# Volant5_Power.net
KiCad netlist of a schematic drawn in Altium Designer
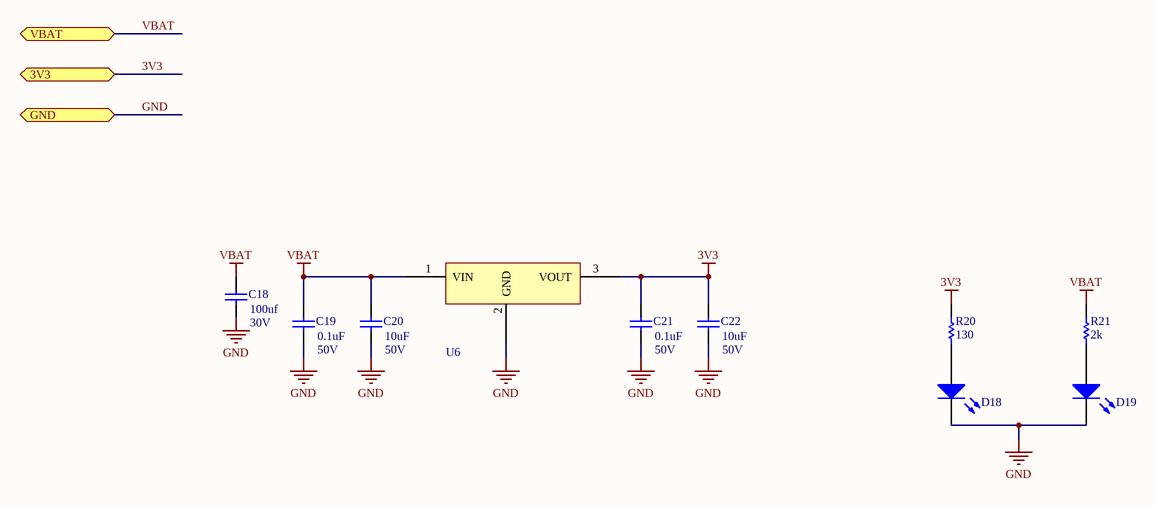
[diagram p0: Volant5.Power.SchDoc]

(export (version "E")
  (design (tool "Eeschema 10.0.6"))
  (components
    (comp (ref "C18")
      (value "100uf")
      (footprint "CS-0603")
      (fields
        (field (name "TOLERANCE") "10%")
        (field (name "VOLTAGE") "30V")
        (field (name "Comment") "CS - CAPACITOR")
      )
      (libsource (lib "CHINOOK_LIBRARY") (part "CS - CAPACITOR"))
    )
    (comp (ref "C19")
      (value "0.1uF")
      (footprint "CS-0603")
      (fields
        (field (name "TOLERANCE") "10%")
        (field (name "VOLTAGE") "50V")
        (field (name "Comment") "CS - CAPACITOR")
      )
      (libsource (lib "CHINOOK_LIBRARY") (part "CS - CAPACITOR"))
    )
    (comp (ref "C20")
      (value "10uF")
      (footprint "CS-0603")
      (fields
        (field (name "TOLERANCE") "10%")
        (field (name "VOLTAGE") "50V")
        (field (name "Comment") "CS - CAPACITOR")
      )
      (libsource (lib "CHINOOK_LIBRARY") (part "CS - CAPACITOR"))
    )
    (comp (ref "C21")
      (value "0.1uF")
      (footprint "CS-0603")
      (fields
        (field (name "TOLERANCE") "10%")
        (field (name "VOLTAGE") "50V")
        (field (name "Comment") "CS - CAPACITOR")
      )
      (libsource (lib "CHINOOK_LIBRARY") (part "CS - CAPACITOR"))
    )
    (comp (ref "C22")
      (value "10uF")
      (footprint "CS-0603")
      (fields
        (field (name "TOLERANCE") "10%")
        (field (name "VOLTAGE") "50V")
        (field (name "Comment") "CS - CAPACITOR")
      )
      (libsource (lib "CHINOOK_LIBRARY") (part "CS - CAPACITOR"))
    )
    (comp (ref "D18")
      (value "LED - NORMAL LED")
      (footprint "LED-0805 YELLOW")
      (libsource (lib "CHINOOK_LIBRARY") (part "LED - NORMAL LED"))
    )
    (comp (ref "D19")
      (value "LED - NORMAL LED")
      (footprint "LED-0805 YELLOW")
      (libsource (lib "CHINOOK_LIBRARY") (part "LED - NORMAL LED"))
    )
    (comp (ref "R20")
      (value "130")
      (footprint "RS-0603")
      (fields
        (field (name "TOLERANCE") "RES TOL")
        (field (name "POWER") "RES POWER")
        (field (name "Comment") "RS - RESISTOR")
      )
      (libsource (lib "CHINOOK_LIBRARY") (part "RS - RESISTOR"))
    )
    (comp (ref "R21")
      (value "2k")
      (footprint "RS-0603")
      (fields
        (field (name "TOLERANCE") "RES TOL")
        (field (name "POWER") "RES POWER")
        (field (name "Comment") "RS - RESISTOR")
      )
      (libsource (lib "CHINOOK_LIBRARY") (part "RS - RESISTOR"))
    )
    (comp (ref "U6")
      (value "OKI-78SR")
      (footprint "IC-OKI78SR-RA")
      (libsource (lib "CHINOOK_LIBRARY") (part "IC - OKI-78SR"))
    )
  )
  (nets
    (net (code "1") (name "3V3") (class "Default")
      (node (ref "C21") (pin "2") (pinfunction "2_2") (pintype "passive"))
      (node (ref "C22") (pin "2") (pinfunction "2_2") (pintype "passive"))
      (node (ref "R20") (pin "2") (pinfunction "2_2") (pintype "passive"))
      (node (ref "U6") (pin "3") (pinfunction "VOUT_3") (pintype "passive"))
    )
    (net (code "2") (name "GND") (class "Default")
      (node (ref "C18") (pin "1") (pinfunction "1_1") (pintype "passive"))
      (node (ref "C19") (pin "1") (pinfunction "1_1") (pintype "passive"))
      (node (ref "C20") (pin "1") (pinfunction "1_1") (pintype "passive"))
      (node (ref "C21") (pin "1") (pinfunction "1_1") (pintype "passive"))
      (node (ref "C22") (pin "1") (pinfunction "1_1") (pintype "passive"))
      (node (ref "D18") (pin "K") (pinfunction "K_K") (pintype "passive"))
      (node (ref "D19") (pin "K") (pinfunction "K_K") (pintype "passive"))
      (node (ref "U6") (pin "2") (pinfunction "GND_2") (pintype "passive"))
    )
    (net (code "3") (name "Net-(D18-PadA)") (class "Default")
      (node (ref "D18") (pin "A") (pinfunction "A_A") (pintype "passive"))
      (node (ref "R20") (pin "1") (pinfunction "1_1") (pintype "passive"))
    )
    (net (code "4") (name "Net-(D19-PadA)") (class "Default")
      (node (ref "D19") (pin "A") (pinfunction "A_A") (pintype "passive"))
      (node (ref "R21") (pin "1") (pinfunction "1_1") (pintype "passive"))
    )
    (net (code "5") (name "VBAT") (class "Default")
      (node (ref "C18") (pin "2") (pinfunction "2_2") (pintype "passive"))
      (node (ref "C19") (pin "2") (pinfunction "2_2") (pintype "passive"))
      (node (ref "C20") (pin "2") (pinfunction "2_2") (pintype "passive"))
      (node (ref "R21") (pin "2") (pinfunction "2_2") (pintype "passive"))
      (node (ref "U6") (pin "1") (pinfunction "VIN_1") (pintype "passive"))
    )
  )
)
